# PF10_Expander.net
KiCad netlist of a schematic drawn in Altium Designer
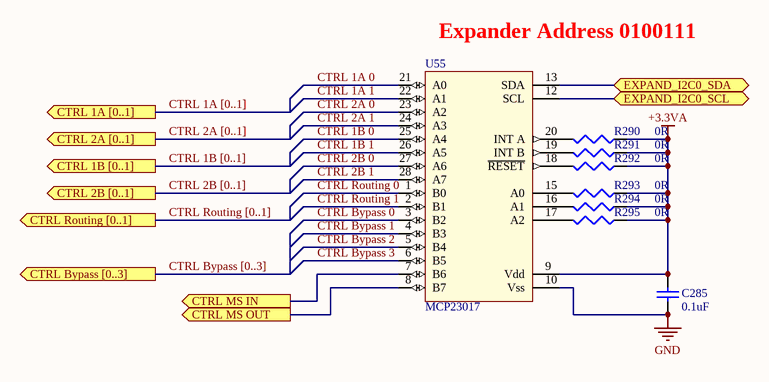
[diagram p0: PF10_Expander.SchDoc]

(export (version "E")
  (design (tool "Eeschema 10.0.6"))
  (components
    (comp (ref "C285")
      (value "0.1uF")
      (footprint "CAPC1608X08")
      (description "Capacitor (Semiconductor SIM Model)")
      (libsource (lib "Michel") (part "Cap Semi"))
    )
    (comp (ref "R290")
      (value "0R")
      (footprint "RESC1608X05")
      (description "Resistor")
      (libsource (lib "Michel") (part "Res3"))
    )
    (comp (ref "R291")
      (value "0R")
      (footprint "RESC1608X05")
      (description "Resistor")
      (libsource (lib "Michel") (part "Res3"))
    )
    (comp (ref "R292")
      (value "0R")
      (footprint "RESC1608X05")
      (description "Resistor")
      (libsource (lib "Michel") (part "Res3"))
    )
    (comp (ref "R293")
      (value "0R")
      (footprint "RESC1608X05")
      (description "Resistor")
      (libsource (lib "Michel") (part "Res3"))
    )
    (comp (ref "R294")
      (value "0R")
      (footprint "RESC1608X05")
      (description "Resistor")
      (libsource (lib "Michel") (part "Res3"))
    )
    (comp (ref "R295")
      (value "0R")
      (footprint "RESC1608X05")
      (description "Resistor")
      (libsource (lib "Michel") (part "Res3"))
    )
    (comp (ref "U55")
      (value "MCP23017")
      (footprint "SOIC28_MCP23017")
      (description "16b I/O Expander")
      (libsource (lib "Michel") (part "MCP23017"))
    )
  )
  (nets
    (net (code "1") (name "+3.3VA") (class "Default")
      (node (ref "C285") (pin "1") (pinfunction "1_1") (pintype "passive"))
      (node (ref "R290") (pin "1") (pinfunction "1_1") (pintype "passive"))
      (node (ref "R291") (pin "1") (pinfunction "1_1") (pintype "passive"))
      (node (ref "R292") (pin "1") (pinfunction "1_1") (pintype "passive"))
      (node (ref "R293") (pin "1") (pinfunction "1_1") (pintype "passive"))
      (node (ref "R294") (pin "1") (pinfunction "1_1") (pintype "passive"))
      (node (ref "R295") (pin "1") (pinfunction "1_1") (pintype "passive"))
      (node (ref "U55") (pin "9") (pinfunction "Vdd_9") (pintype "power_in"))
    )
    (net (code "2") (name "/CTRL 1A 0") (class "Default")
      (node (ref "U55") (pin "21") (pinfunction "A0_21") (pintype "bidirectional"))
    )
    (net (code "3") (name "/CTRL 1A 1") (class "Default")
      (node (ref "U55") (pin "22") (pinfunction "A1_22") (pintype "bidirectional"))
    )
    (net (code "4") (name "/CTRL 1B 0") (class "Default")
      (node (ref "U55") (pin "25") (pinfunction "A4_25") (pintype "bidirectional"))
    )
    (net (code "5") (name "/CTRL 1B 1") (class "Default")
      (node (ref "U55") (pin "26") (pinfunction "A5_26") (pintype "bidirectional"))
    )
    (net (code "6") (name "/CTRL 2A 0") (class "Default")
      (node (ref "U55") (pin "23") (pinfunction "A2_23") (pintype "bidirectional"))
    )
    (net (code "7") (name "/CTRL 2A 1") (class "Default")
      (node (ref "U55") (pin "24") (pinfunction "A3_24") (pintype "bidirectional"))
    )
    (net (code "8") (name "/CTRL 2B 0") (class "Default")
      (node (ref "U55") (pin "27") (pinfunction "A6_27") (pintype "bidirectional"))
    )
    (net (code "9") (name "/CTRL 2B 1") (class "Default")
      (node (ref "U55") (pin "28") (pinfunction "A7_28") (pintype "bidirectional"))
    )
    (net (code "10") (name "/CTRL Bypass 0") (class "Default")
      (node (ref "U55") (pin "3") (pinfunction "B2_3") (pintype "bidirectional"))
    )
    (net (code "11") (name "/CTRL Bypass 1") (class "Default")
      (node (ref "U55") (pin "4") (pinfunction "B3_4") (pintype "bidirectional"))
    )
    (net (code "12") (name "/CTRL Bypass 2") (class "Default")
      (node (ref "U55") (pin "5") (pinfunction "B4_5") (pintype "bidirectional"))
    )
    (net (code "13") (name "/CTRL Bypass 3") (class "Default")
      (node (ref "U55") (pin "6") (pinfunction "B5_6") (pintype "bidirectional"))
    )
    (net (code "14") (name "/CTRL MS IN") (class "Default")
      (node (ref "U55") (pin "7") (pinfunction "B6_7") (pintype "bidirectional"))
    )
    (net (code "15") (name "/CTRL MS OUT") (class "Default")
      (node (ref "U55") (pin "8") (pinfunction "B7_8") (pintype "bidirectional"))
    )
    (net (code "16") (name "/CTRL Routing 0") (class "Default")
      (node (ref "U55") (pin "1") (pinfunction "B0_1") (pintype "bidirectional"))
    )
    (net (code "17") (name "/CTRL Routing 1") (class "Default")
      (node (ref "U55") (pin "2") (pinfunction "B1_2") (pintype "bidirectional"))
    )
    (net (code "18") (name "/EXPAND_I2C0_SCL") (class "Default")
      (node (ref "U55") (pin "12") (pinfunction "SCL_12") (pintype "passive"))
    )
    (net (code "19") (name "/EXPAND_I2C0_SDA") (class "Default")
      (node (ref "U55") (pin "13") (pinfunction "SDA_13") (pintype "passive"))
    )
    (net (code "26") (name "GND") (class "Default")
      (node (ref "C285") (pin "2") (pinfunction "2_2") (pintype "passive"))
      (node (ref "U55") (pin "10") (pinfunction "Vss_10") (pintype "power_in"))
    )
    (net (code "27") (name "Net-(R293-Pad2)") (class "Default")
      (node (ref "R293") (pin "2") (pinfunction "2_2") (pintype "passive"))
      (node (ref "U55") (pin "15") (pinfunction "A0_15") (pintype "passive"))
    )
    (net (code "28") (name "Net-(R294-Pad2)") (class "Default")
      (node (ref "R294") (pin "2") (pinfunction "2_2") (pintype "passive"))
      (node (ref "U55") (pin "16") (pinfunction "A1_16") (pintype "passive"))
    )
    (net (code "29") (name "Net-(R295-Pad2)") (class "Default")
      (node (ref "R295") (pin "2") (pinfunction "2_2") (pintype "passive"))
      (node (ref "U55") (pin "17") (pinfunction "A2_17") (pintype "passive"))
    )
    (net (code "30") (name "Net-(U55-INT_A)") (class "Default")
      (node (ref "R290") (pin "2") (pinfunction "2_2") (pintype "passive"))
      (node (ref "U55") (pin "20") (pinfunction "INT_A_20") (pintype "output"))
    )
    (net (code "31") (name "Net-(U55-INT_B)") (class "Default")
      (node (ref "R291") (pin "2") (pinfunction "2_2") (pintype "passive"))
      (node (ref "U55") (pin "19") (pinfunction "INT_B_19") (pintype "output"))
    )
    (net (code "32") (name "Net-(U55-~{RESET})") (class "Default")
      (node (ref "R292") (pin "2") (pinfunction "2_2") (pintype "passive"))
      (node (ref "U55") (pin "18") (pinfunction "~{RESET}_18") (pintype "output"))
    )
  )
)
